# led_RGB.net
KiCad netlist of a schematic drawn in Altium Designer
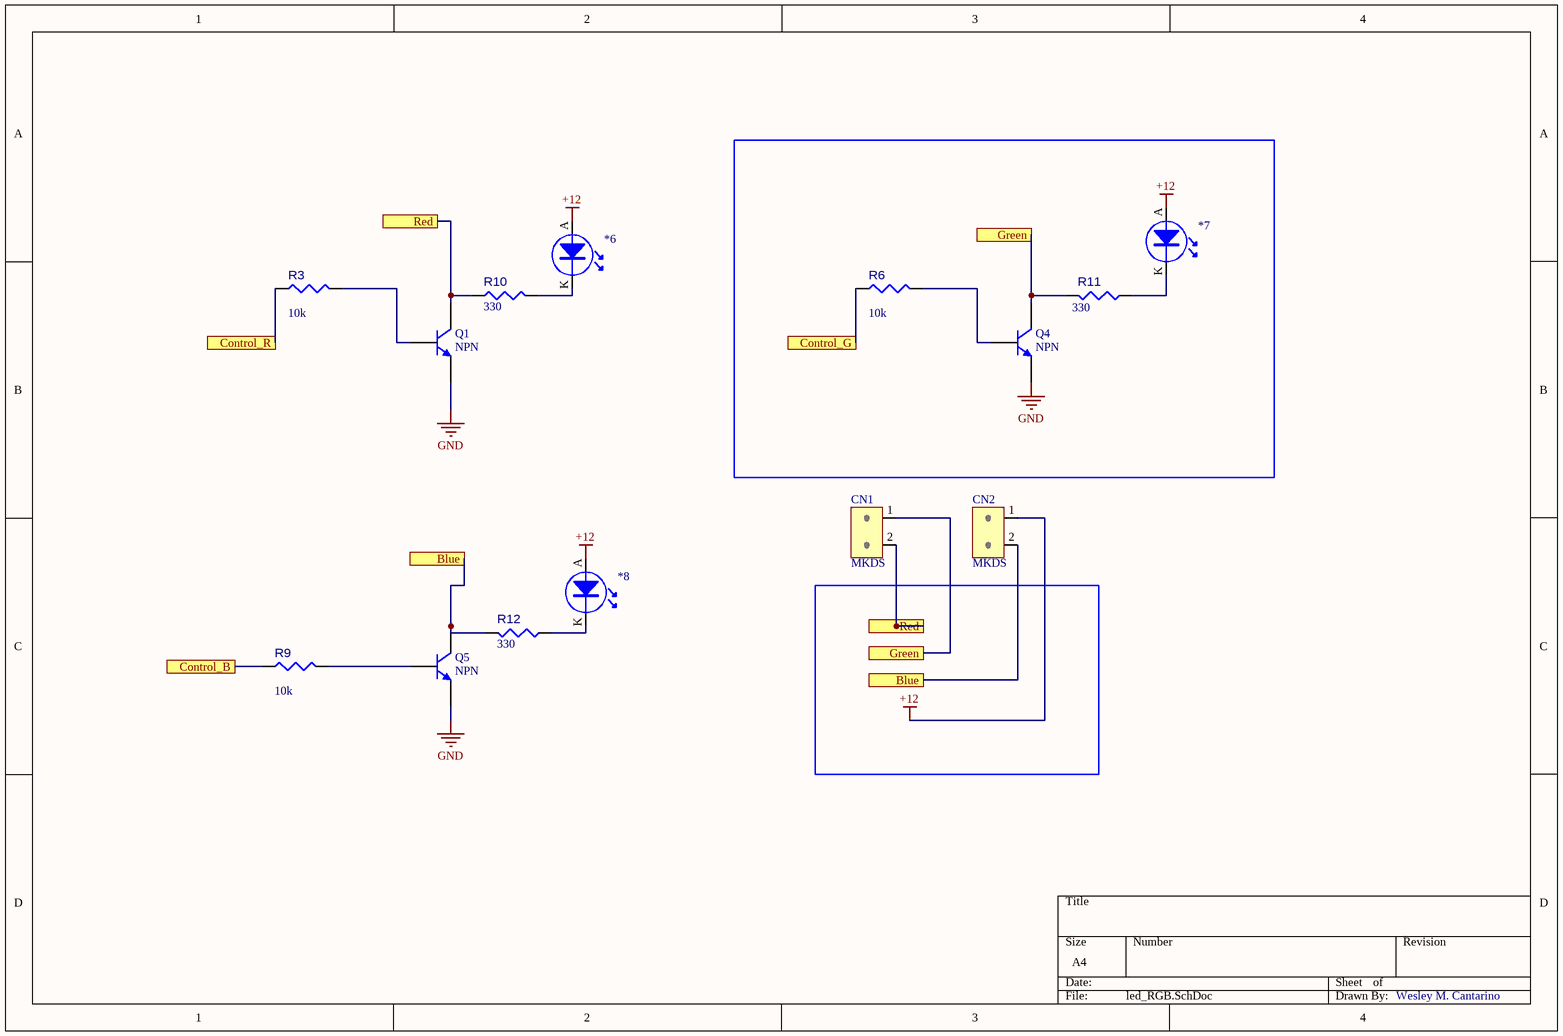
[diagram p0: led_RGB.SchDoc]

(export (version "E")
  (design (tool "Eeschema 10.0.6"))
  (components
    (comp (ref "*6")
      (value "LED_AXIAL_5MM")
      (footprint "HEADER_1X2")
      (libsource (lib "i9Library_Altium") (part "LED_AXIAL_5MM"))
    )
    (comp (ref "*7")
      (value "LED_AXIAL_5MM")
      (footprint "HEADER_1X2")
      (libsource (lib "i9Library_Altium") (part "LED_AXIAL_5MM"))
    )
    (comp (ref "*8")
      (value "LED_AXIAL_5MM")
      (footprint "HEADER_1X2")
      (libsource (lib "i9Library_Altium") (part "LED_AXIAL_5MM"))
    )
    (comp (ref "CN1") (value "MKDS") (footprint "MKDSN02") (libsource (lib "i9Library_v1.7.5") (part "CN_2")))
    (comp (ref "CN2") (value "MKDS") (footprint "MKDSN02") (libsource (lib "i9Library_v1.7.5") (part "CN_2")))
    (comp (ref "Q1")
      (value "NPN")
      (footprint "HEADER_1X3")
      (description "NPN Bipolar Transistor")
      (fields (field (name "PUBLISHER") "Altium Limited"))
      (libsource (lib "Miscellaneous Devices") (part "NPN"))
    )
    (comp (ref "Q4")
      (value "NPN")
      (footprint "HEADER_1X3")
      (description "NPN Bipolar Transistor")
      (fields (field (name "PUBLISHER") "Altium Limited"))
      (libsource (lib "Miscellaneous Devices") (part "NPN"))
    )
    (comp (ref "Q5")
      (value "NPN")
      (footprint "HEADER_1X3")
      (description "NPN Bipolar Transistor")
      (fields (field (name "PUBLISHER") "Altium Limited"))
      (libsource (lib "Miscellaneous Devices") (part "NPN"))
    )
    (comp (ref "R3")
      (value "10k")
      (footprint "RES_PTH_7.62MM")
      (description "Pin Through Hole Resistor 7.62mm")
      (libsource (lib "i9Library_Altium") (part "RES_PTH_7.62MM"))
    )
    (comp (ref "R6")
      (value "10k")
      (footprint "RES_PTH_7.62MM")
      (description "Pin Through Hole Resistor 7.62mm")
      (libsource (lib "i9Library_Altium") (part "RES_PTH_7.62MM"))
    )
    (comp (ref "R9")
      (value "10k")
      (footprint "RES_PTH_7.62MM")
      (description "Pin Through Hole Resistor 7.62mm")
      (libsource (lib "i9Library_Altium") (part "RES_PTH_7.62MM"))
    )
    (comp (ref "R10")
      (value "330")
      (footprint "RES_PTH_7.62MM")
      (description "Pin Through Hole Resistor 7.62mm")
      (libsource (lib "i9Library_Altium") (part "RES_PTH_7.62MM"))
    )
    (comp (ref "R11")
      (value "330")
      (footprint "RES_PTH_7.62MM")
      (description "Pin Through Hole Resistor 7.62mm")
      (libsource (lib "i9Library_Altium") (part "RES_PTH_7.62MM"))
    )
    (comp (ref "R12")
      (value "330")
      (footprint "RES_PTH_7.62MM")
      (description "Pin Through Hole Resistor 7.62mm")
      (libsource (lib "i9Library_Altium") (part "RES_PTH_7.62MM"))
    )
  )
  (nets
    (net (code "1") (name "+12") (class "Default")
      (node (ref "*6") (pin "A") (pintype "passive"))
      (node (ref "*7") (pin "A") (pintype "passive"))
      (node (ref "*8") (pin "A") (pintype "passive"))
      (node (ref "CN2") (pin "1") (pintype "passive"))
    )
    (net (code "2") (name "/Blue") (class "Default")
      (node (ref "CN2") (pin "2") (pinfunction "2_2") (pintype "passive"))
      (node (ref "Q5") (pin "1") (pinfunction "C_1") (pintype "passive"))
      (node (ref "R12") (pin "2") (pinfunction "2_2") (pintype "passive"))
    )
    (net (code "3") (name "/Control_B") (class "Default")
      (node (ref "R9") (pin "1") (pinfunction "1_1") (pintype "passive"))
    )
    (net (code "4") (name "/Control_G") (class "Default")
      (node (ref "R6") (pin "1") (pinfunction "1_1") (pintype "passive"))
    )
    (net (code "5") (name "/Control_R") (class "Default")
      (node (ref "R3") (pin "1") (pinfunction "1_1") (pintype "passive"))
    )
    (net (code "6") (name "/Green") (class "Default")
      (node (ref "CN1") (pin "1") (pintype "passive"))
      (node (ref "Q4") (pin "1") (pinfunction "C_1") (pintype "passive"))
      (node (ref "R11") (pin "2") (pinfunction "2_2") (pintype "passive"))
    )
    (net (code "7") (name "/Red") (class "Default")
      (node (ref "CN1") (pin "2") (pinfunction "2_2") (pintype "passive"))
      (node (ref "Q1") (pin "1") (pinfunction "C_1") (pintype "passive"))
      (node (ref "R10") (pin "1") (pinfunction "1_1") (pintype "passive"))
    )
    (net (code "8") (name "GND") (class "Default")
      (node (ref "Q1") (pin "3") (pinfunction "E_3") (pintype "passive"))
      (node (ref "Q4") (pin "3") (pinfunction "E_3") (pintype "passive"))
      (node (ref "Q5") (pin "3") (pinfunction "E_3") (pintype "passive"))
    )
    (net (code "9") (name "Net-(*6-PadK)") (class "Default")
      (node (ref "*6") (pin "K") (pintype "passive"))
      (node (ref "R10") (pin "2") (pinfunction "2_2") (pintype "passive"))
    )
    (net (code "10") (name "Net-(*7-PadK)") (class "Default")
      (node (ref "*7") (pin "K") (pintype "passive"))
      (node (ref "R11") (pin "1") (pinfunction "1_1") (pintype "passive"))
    )
    (net (code "11") (name "Net-(*8-PadK)") (class "Default")
      (node (ref "*8") (pin "K") (pintype "passive"))
      (node (ref "R12") (pin "1") (pinfunction "1_1") (pintype "passive"))
    )
    (net (code "12") (name "Net-(Q1-B)") (class "Default")
      (node (ref "Q1") (pin "2") (pinfunction "B_2") (pintype "passive"))
      (node (ref "R3") (pin "2") (pinfunction "2_2") (pintype "passive"))
    )
    (net (code "13") (name "Net-(Q4-B)") (class "Default")
      (node (ref "Q4") (pin "2") (pinfunction "B_2") (pintype "passive"))
      (node (ref "R6") (pin "2") (pinfunction "2_2") (pintype "passive"))
    )
    (net (code "14") (name "Net-(Q5-B)") (class "Default")
      (node (ref "Q5") (pin "2") (pinfunction "B_2") (pintype "passive"))
      (node (ref "R9") (pin "2") (pinfunction "2_2") (pintype "passive"))
    )
  )
)
